# RaumluftsensorC3.net
KiCad netlist of a schematic drawn in Altium Designer
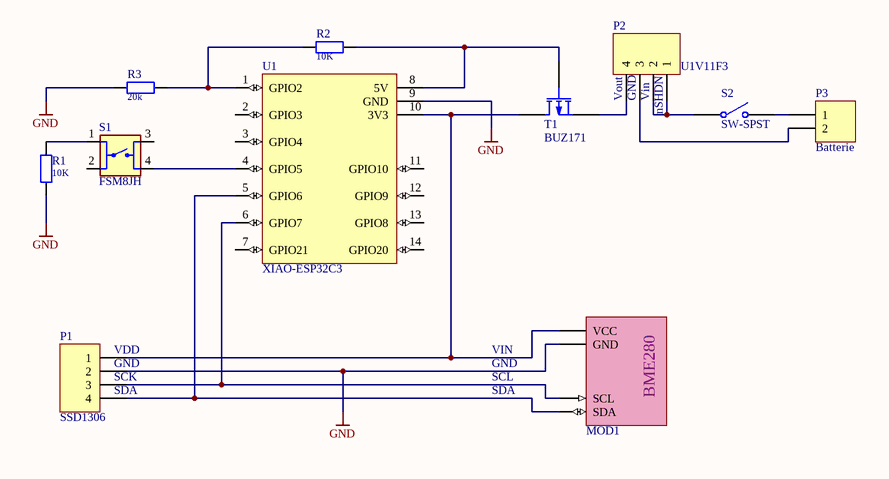
[diagram p0: RaumluftsensorC3.SchDoc]

(export (version "E")
  (design (tool "Eeschema 10.0.6"))
  (components
    (comp (ref "MOD1")
      (value "BME280")
      (footprint "BME280")
      (description "Bosch BME280 Module GY-BME280-3.3")
      (fields (field (name "PUBLISHER") "Michael Kupfner"))
      (libsource (lib "HTLinn_Miscellaneous") (part "BME280"))
    )
    (comp (ref "P1")
      (value "SSD1306")
      (footprint "HDR1X4")
      (description "OLED SSD1306 - Display")
      (fields (field (name "PUBLISHER") "Altium Limited"))
      (libsource (lib "Miscellaneous Connectors") (part "Header 4"))
    )
    (comp (ref "P2")
      (value "U1V11F3")
      (footprint "HDR1X4")
      (description "Pololu U1V11F3")
      (fields (field (name "PUBLISHER") "Altium Limited"))
      (libsource (lib "") (part "Header 4_1"))
    )
    (comp (ref "P3")
      (value "Batterie")
      (footprint "HDR1X2")
      (description "Batteriehalter")
      (fields (field (name "PUBLISHER") "Altium Limited"))
      (libsource (lib "Miscellaneous Connectors") (part "Header 2"))
    )
    (comp (ref "R1")
      (value "10K")
      (footprint "R_0207/RM4")
      (description "Resistor")
      (libsource (lib "HTLInn_RLCQ") (part "R"))
    )
    (comp (ref "R2")
      (value "10K")
      (footprint "R_0207/RM4")
      (description "Resistor")
      (libsource (lib "") (part "R_2"))
    )
    (comp (ref "R3")
      (value "20k")
      (footprint "R_0207/RM4")
      (description "Resistor")
      (libsource (lib "") (part "R_1"))
    )
    (comp (ref "S1")
      (value "FSM8JH")
      (footprint "SW_FSM8JH")
      (description "Tactile Switch SPST-NO Top Actuated Through Hole")
      (fields (field (name "MF") "TE Connectivity"))
      (libsource (lib "FSM8JH") (part "FSM8JH"))
    )
    (comp (ref "S2")
      (value "SW-SPST")
      (footprint "SPST-2")
      (description "Single-Pole, Single-Throw Switch")
      (fields (field (name "PUBLISHER") "Altium Limited"))
      (libsource (lib "Miscellaneous Devices") (part "SW-SPST"))
    )
    (comp (ref "T1")
      (value "BUZ171")
      (description "P-Channel MOSFET")
      (fields (field (name "PUBLISHER") "Michael Kupfner"))
      (libsource (lib "HTLinn_FET") (part "BUZ171"))
    )
    (comp (ref "U1")
      (value "XIAO-ESP32C3")
      (footprint "PCBComponent_1")
      (libsource (lib "XIAO ESP32C3") (part "XIAO-ESP32C3"))
    )
  )
  (nets
    (net (code "1") (name "GND") (class "Default")
      (node (ref "MOD1") (pin "2") (pinfunction "GND_2") (pintype "power_in"))
      (node (ref "P1") (pin "2") (pinfunction "2_2") (pintype "passive"))
      (node (ref "R1") (pin "1") (pinfunction "1_1") (pintype "passive"))
      (node (ref "R3") (pin "1") (pinfunction "1_1") (pintype "passive"))
      (node (ref "U1") (pin "9") (pinfunction "GND_9") (pintype "power_in"))
    )
    (net (code "2") (name "Net-(MOD1-SCL)") (class "Default")
      (node (ref "MOD1") (pin "3") (pinfunction "SCL_3") (pintype "input"))
      (node (ref "P1") (pin "3") (pinfunction "3_3") (pintype "passive"))
      (node (ref "U1") (pin "6") (pinfunction "GPIO7_6") (pintype "bidirectional"))
    )
    (net (code "3") (name "Net-(MOD1-SDA)") (class "Default")
      (node (ref "MOD1") (pin "4") (pinfunction "SDA_4") (pintype "bidirectional"))
      (node (ref "P1") (pin "4") (pinfunction "4_4") (pintype "passive"))
      (node (ref "U1") (pin "5") (pinfunction "GPIO6_5") (pintype "bidirectional"))
    )
    (net (code "4") (name "Net-(MOD1-VCC)") (class "Default")
      (node (ref "MOD1") (pin "1") (pinfunction "VCC_1") (pintype "power_in"))
      (node (ref "P1") (pin "1") (pinfunction "1_1") (pintype "passive"))
      (node (ref "T1") (pin "3") (pinfunction "D_3") (pintype "passive"))
      (node (ref "U1") (pin "10") (pinfunction "3V3_10") (pintype "power_in"))
    )
    (net (code "5") (name "Net-(P2-Pad3)") (class "Default")
      (node (ref "P2") (pin "3") (pinfunction "3_3") (pintype "passive"))
      (node (ref "P3") (pin "2") (pinfunction "2_2") (pintype "passive"))
    )
    (net (code "6") (name "Net-(R1-Pad2)") (class "Default")
      (node (ref "R1") (pin "2") (pinfunction "2_2") (pintype "passive"))
      (node (ref "S1") (pin "1") (pinfunction "1_1") (pintype "passive"))
    )
    (net (code "7") (name "Net-(S2-COMMON)") (class "Default")
      (node (ref "P2") (pin "1") (pinfunction "1_1") (pintype "passive"))
      (node (ref "P2") (pin "2") (pinfunction "2_2") (pintype "passive"))
      (node (ref "S2") (pin "1") (pinfunction "COMMON_1") (pintype "passive"))
    )
    (net (code "8") (name "Net-(S2-NO)") (class "Default")
      (node (ref "P3") (pin "1") (pinfunction "1_1") (pintype "passive"))
      (node (ref "S2") (pin "2") (pinfunction "NO_2") (pintype "passive"))
    )
    (net (code "9") (name "Net-(T1-G)") (class "Default")
      (node (ref "R2") (pin "1") (pinfunction "1_1") (pintype "passive"))
      (node (ref "T1") (pin "1") (pinfunction "G_1") (pintype "passive"))
      (node (ref "U1") (pin "8") (pinfunction "5V_8") (pintype "power_in"))
    )
    (net (code "10") (name "Net-(T1-S)") (class "Default")
      (node (ref "P2") (pin "4") (pinfunction "4_4") (pintype "passive"))
      (node (ref "T1") (pin "2") (pinfunction "S_2") (pintype "passive"))
    )
    (net (code "11") (name "Net-(U1-GPIO2)") (class "Default")
      (node (ref "R2") (pin "2") (pinfunction "2_2") (pintype "passive"))
      (node (ref "R3") (pin "2") (pinfunction "2_2") (pintype "passive"))
      (node (ref "U1") (pin "1") (pinfunction "GPIO2_1") (pintype "bidirectional"))
    )
    (net (code "12") (name "Net-(U1-GPIO5)") (class "Default")
      (node (ref "S1") (pin "4") (pinfunction "4_4") (pintype "passive"))
      (node (ref "U1") (pin "4") (pinfunction "GPIO5_4") (pintype "bidirectional"))
    )
    (net (code "13") (name "unconnected-(S1-Pad2)") (class "Default")
      (node (ref "S1") (pin "2") (pinfunction "2_2") (pintype "passive"))
    )
    (net (code "14") (name "unconnected-(S1-Pad3)") (class "Default")
      (node (ref "S1") (pin "3") (pinfunction "3_3") (pintype "passive"))
    )
    (net (code "15") (name "unconnected-(U1-GPIO3-Pad2)") (class "Default")
      (node (ref "U1") (pin "2") (pinfunction "GPIO3_2") (pintype "bidirectional"))
    )
    (net (code "16") (name "unconnected-(U1-GPIO4-Pad3)") (class "Default")
      (node (ref "U1") (pin "3") (pinfunction "GPIO4_3") (pintype "bidirectional"))
    )
    (net (code "17") (name "unconnected-(U1-GPIO8-Pad13)") (class "Default")
      (node (ref "U1") (pin "13") (pinfunction "GPIO8_13") (pintype "bidirectional"))
    )
    (net (code "18") (name "unconnected-(U1-GPIO9-Pad12)") (class "Default")
      (node (ref "U1") (pin "12") (pinfunction "GPIO9_12") (pintype "bidirectional"))
    )
    (net (code "19") (name "unconnected-(U1-GPIO10-Pad11)") (class "Default")
      (node (ref "U1") (pin "11") (pinfunction "GPIO10_11") (pintype "bidirectional"))
    )
    (net (code "20") (name "unconnected-(U1-GPIO20-Pad14)") (class "Default")
      (node (ref "U1") (pin "14") (pinfunction "GPIO20_14") (pintype "bidirectional"))
    )
    (net (code "21") (name "unconnected-(U1-GPIO21-Pad7)") (class "Default")
      (node (ref "U1") (pin "7") (pinfunction "GPIO21_7") (pintype "bidirectional"))
    )
  )
)
